# SensWear_MCU.net
KiCad netlist of a schematic drawn in Altium Designer
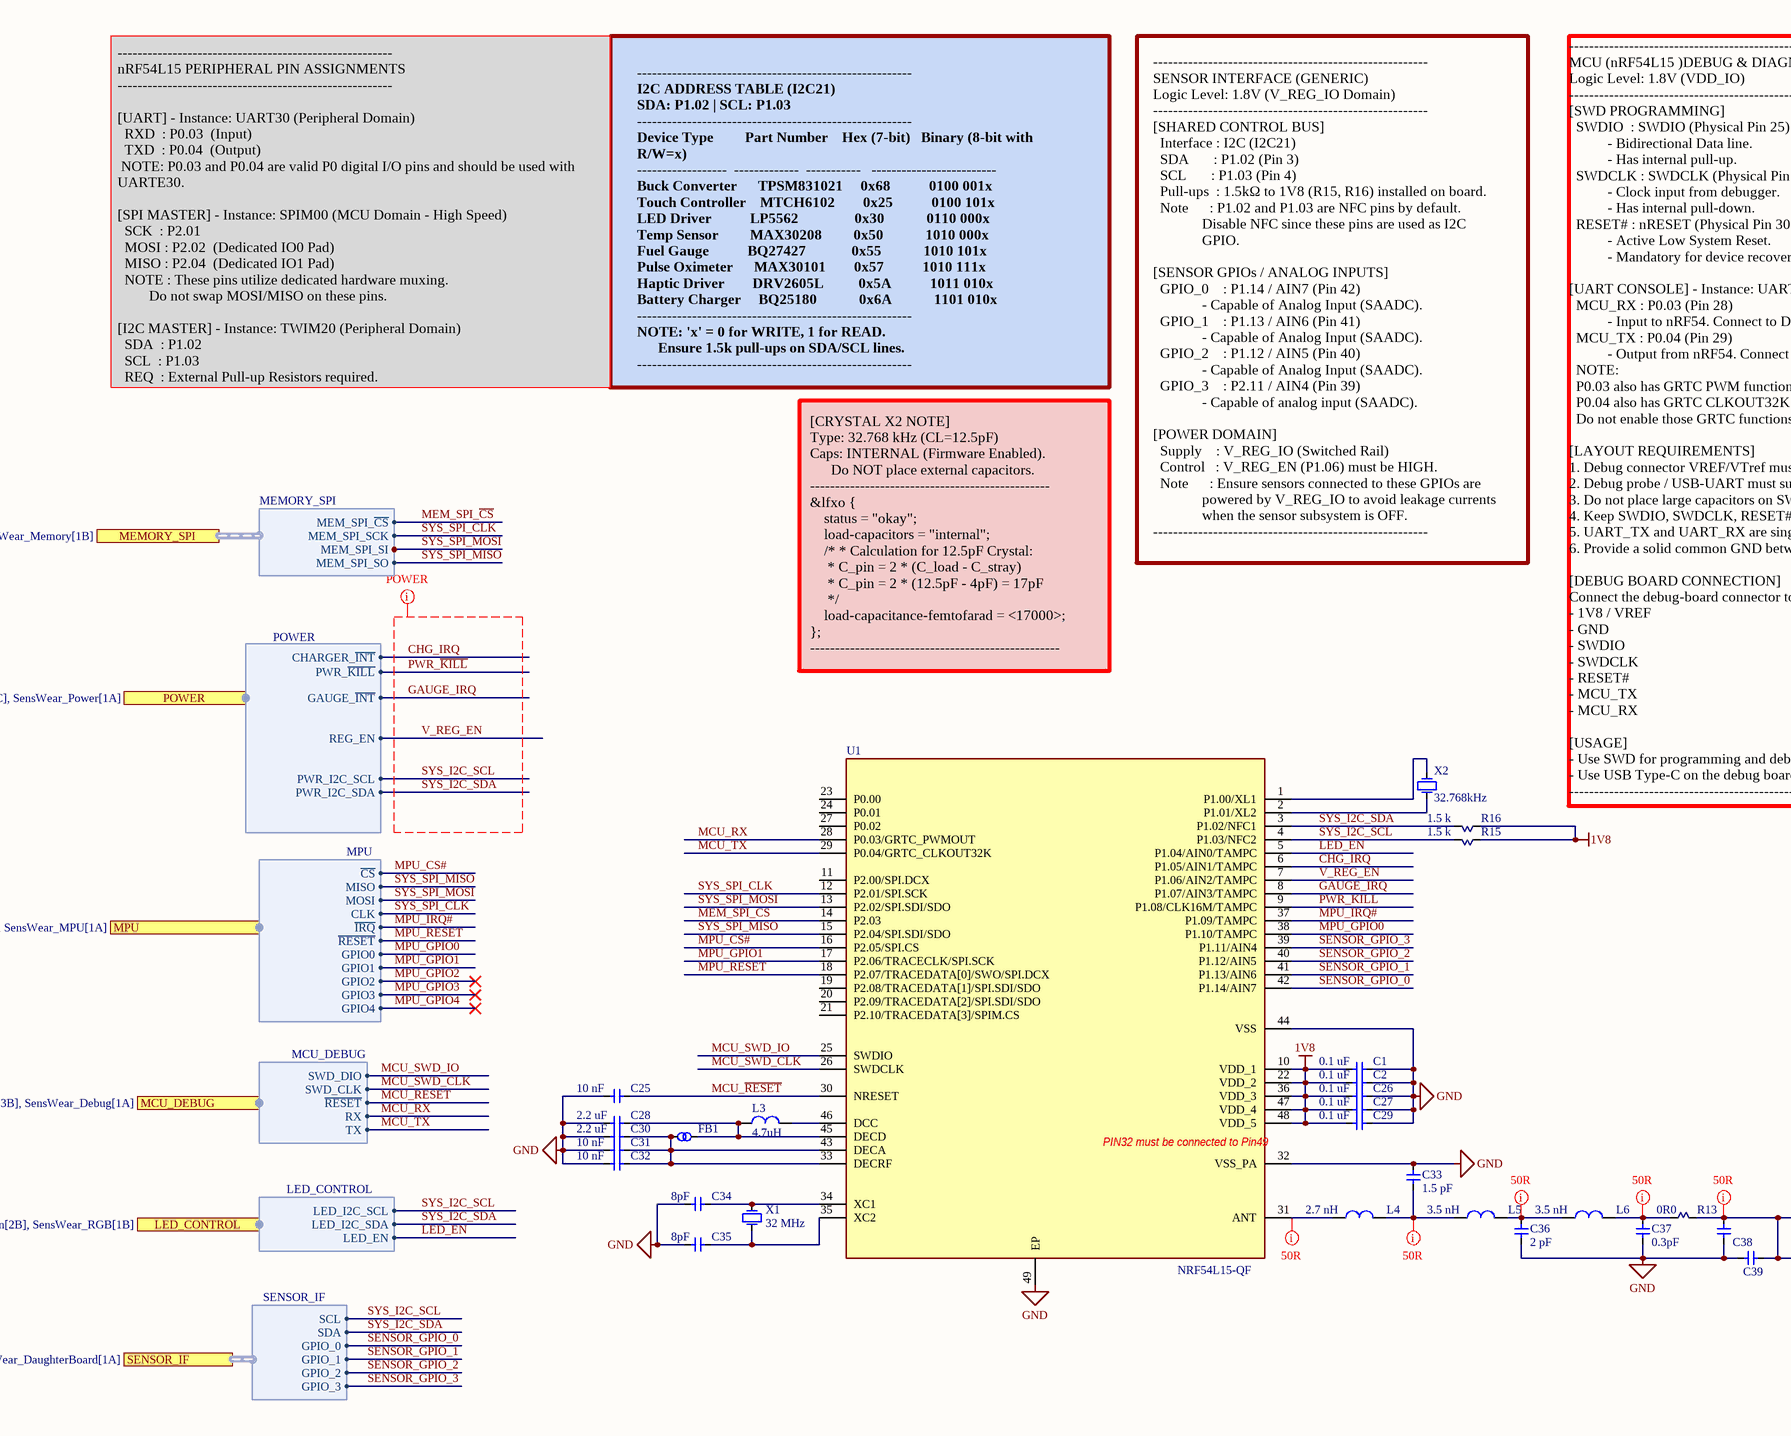
[diagram p0: SensWear_MCU.SchDoc, left]
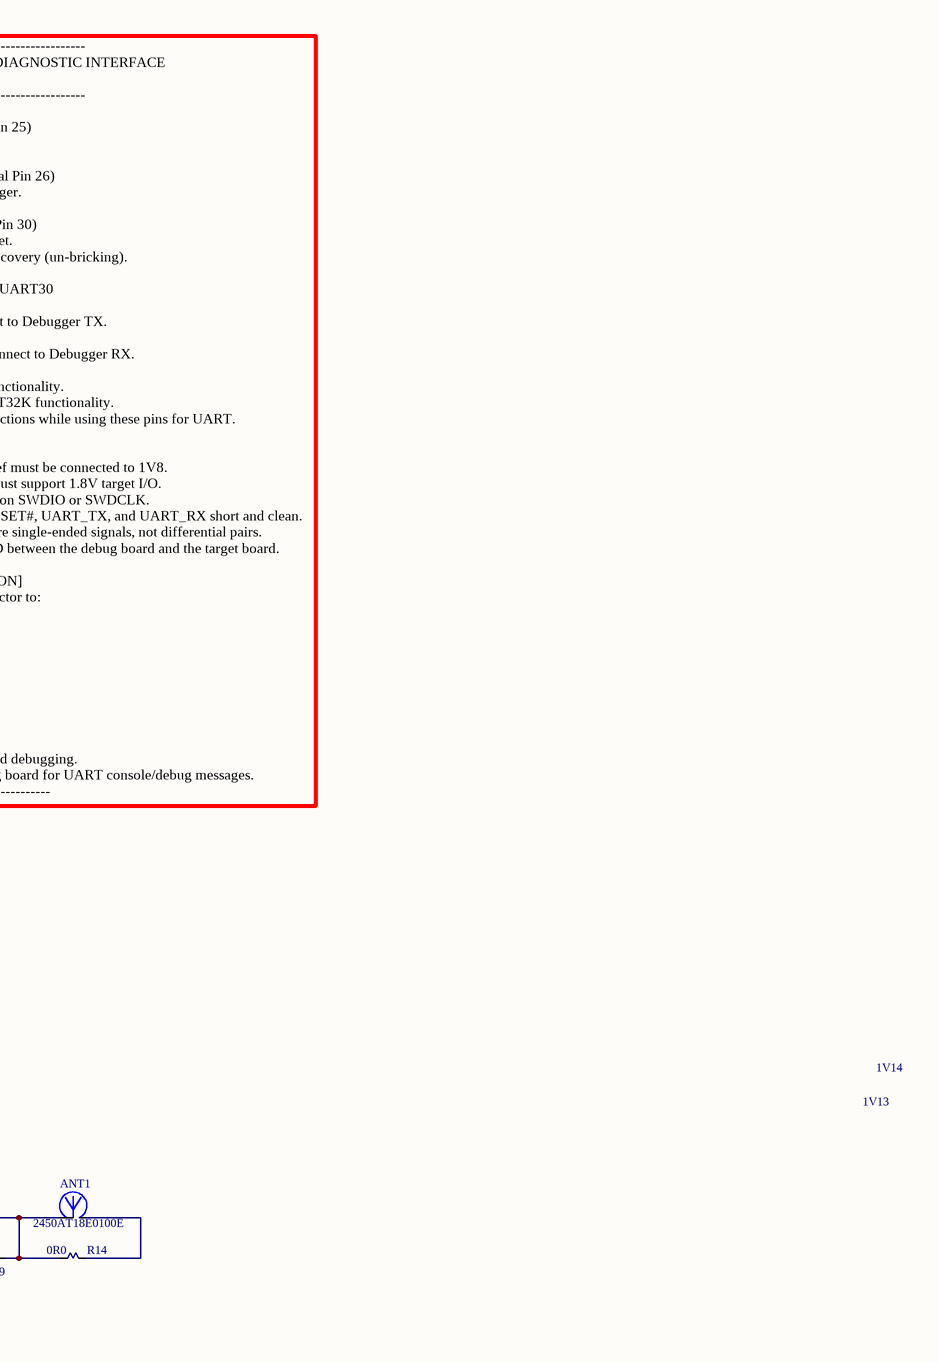
[diagram p1: SensWear_MCU.SchDoc, right]

(export (version "E")
  (design (tool "Eeschema 10.0.6"))
  (components
    (comp (ref "ANT1")
      (value "2450AT18E0100E")
      (footprint "ANTC3216X130N")
      (description "7 Inch Reel / Mini 2.45Ghz Chip Antenna")
      (fields (field (name "MANUFACTURER") "Johanson") (field (name "CHECKED") "TRUE"))
      (libsource (lib "SensWearComponents") (part "2450AT18E0100E"))
    )
    (comp (ref "C1")
      (value "0.1 uF")
      (footprint "CAPC1005X05N")
      (description "CAP CER 0.1UF 16V X5R 0402")
      (fields
        (field (name "MANUFACTURER") "Murata Electronics")
        (field (name "MANUFACTURER PART NUMBER") "GRM155R61C104KA88D")
      )
      (libsource (lib "SensWearComponents") (part "GRM155R61C104KA88D__2"))
    )
    (comp (ref "C2")
      (value "0.1 uF")
      (footprint "CAPC1005X05N")
      (description "CAP CER 0.1UF 16V X5R 0402")
      (fields
        (field (name "MANUFACTURER") "Murata Electronics")
        (field (name "MANUFACTURER PART NUMBER") "GRM155R61C104KA88D")
      )
      (libsource (lib "SensWearComponents") (part "GRM155R61C104KA88D__2"))
    )
    (comp (ref "C25")
      (value "10 nF")
      (footprint "CAPC1005X05N")
      (description "CAP CER 10000PF 50V X7R 0402")
      (fields
        (field (name "MANUFACTURER") "Murata Electronics North America")
        (field (name "MANUFACTURER PART NUMBER") "GRM155R71H103KA88D")
      )
      (libsource (lib "SensWearComponents") (part "GRM155R71H103KA88D"))
    )
    (comp (ref "C26")
      (value "0.1 uF")
      (footprint "CAPC1005X05N")
      (description "CAP CER 0.1UF 16V X5R 0402")
      (fields
        (field (name "MANUFACTURER") "Murata Electronics")
        (field (name "MANUFACTURER PART NUMBER") "GRM155R61C104KA88D")
      )
      (libsource (lib "SensWearComponents") (part "GRM155R61C104KA88D__2"))
    )
    (comp (ref "C27")
      (value "0.1 uF")
      (footprint "CAPC1005X05N")
      (description "CAP CER 0.1UF 16V X5R 0402")
      (fields
        (field (name "MANUFACTURER") "Murata Electronics")
        (field (name "MANUFACTURER PART NUMBER") "GRM155R61C104KA88D")
      )
      (libsource (lib "SensWearComponents") (part "GRM155R61C104KA88D__2"))
    )
    (comp (ref "C28")
      (value "2.2 uF")
      (footprint "CAPC1005X05N")
      (description "CAP CER 2.2UF 10V X5R 0402")
      (fields
        (field (name "MANUFACTURER") "Murata Electronics North America")
        (field (name "MANUFACTURER PART NUMBER") "GRM155R61A225KE95D")
      )
      (libsource (lib "SensWearComponents") (part "GRM155R61A225KE95D"))
    )
    (comp (ref "C29")
      (value "0.1 uF")
      (footprint "CAPC1005X05N")
      (description "CAP CER 0.1UF 16V X5R 0402")
      (fields
        (field (name "MANUFACTURER") "Murata Electronics")
        (field (name "MANUFACTURER PART NUMBER") "GRM155R61C104KA88D")
      )
      (libsource (lib "SensWearComponents") (part "GRM155R61C104KA88D__2"))
    )
    (comp (ref "C30")
      (value "2.2 uF")
      (footprint "CAPC1005X05N")
      (description "CAP CER 2.2UF 10V X5R 0402")
      (fields
        (field (name "MANUFACTURER") "Murata Electronics North America")
        (field (name "MANUFACTURER PART NUMBER") "GRM155R61A225KE95D")
      )
      (libsource (lib "SensWearComponents") (part "GRM155R61A225KE95D"))
    )
    (comp (ref "C31")
      (value "10 nF")
      (footprint "CAPC1005X05N")
      (description "CAP CER 10000PF 50V X7R 0402")
      (fields
        (field (name "MANUFACTURER") "Murata Electronics North America")
        (field (name "MANUFACTURER PART NUMBER") "GRM155R71H103KA88D")
      )
      (libsource (lib "SensWearComponents") (part "GRM155R71H103KA88D"))
    )
    (comp (ref "C32")
      (value "10 nF")
      (footprint "CAPC1005X05N")
      (description "CAP CER 10000PF 50V X7R 0402")
      (fields
        (field (name "MANUFACTURER") "Murata Electronics North America")
        (field (name "MANUFACTURER PART NUMBER") "GRM155R71H103KA88D")
      )
      (libsource (lib "SensWearComponents") (part "GRM155R71H103KA88D"))
    )
    (comp (ref "C33")
      (value "1.5 pF")
      (footprint "CAPC1005X05N")
      (description "Multilayer Ceramic Capacitor, 1.5 pF, 50 V, ï¿½ 0.1pF, C0G (NP0), 0402 [1005 Metric]")
      (fields
        (field (name "MANUFACTURER") "Murata")
        (field (name "MANUFACTURER PART NUMBER") "GJM1555C1H1R5BB01D")
      )
      (libsource (lib "SensWearComponents") (part "GJM1555C1H1R5BB01D"))
    )
    (comp (ref "C34")
      (value "8pF")
      (footprint "CAPC1005X05N")
      (description "Multilayer Ceramic Capacitors MLCC - SMD/SMT 0402 8.0pF 50volts C0G +/-0.05pF")
      (fields
        (field (name "MANUFACTURER") "Murata")
        (field (name "MANUFACTURER PART NUMBER") "GRM1555C1H8R0BA01D")
      )
      (libsource (lib "SensWearComponents") (part "GRM1555C1H8R0BA01D"))
    )
    (comp (ref "C35")
      (value "8pF")
      (footprint "CAPC1005X05N")
      (description "Multilayer Ceramic Capacitors MLCC - SMD/SMT 0402 8.0pF 50volts C0G +/-0.05pF")
      (fields
        (field (name "MANUFACTURER") "Murata")
        (field (name "MANUFACTURER PART NUMBER") "GRM1555C1H8R0BA01D")
      )
      (libsource (lib "SensWearComponents") (part "GRM1555C1H8R0BA01D"))
    )
    (comp (ref "C36")
      (value "2 pF")
      (footprint "CAPC1005X05N")
      (description "0402 2 pF 50V ±0.05 pF Tolerance C0G SMT Multilayer Ceramic Capacitor")
      (fields
        (field (name "MANUFACTURER") "Murata")
        (field (name "MANUFACTURER PART NUMBER") "GJM1555C1H2R0WB01D")
      )
      (libsource (lib "SensWearComponents") (part "GJM1555C1H2R0WB01D"))
    )
    (comp (ref "C37")
      (value "0.3pF")
      (footprint "INDC1005X06N")
      (description "0402 0.3 pF 50V ±0.05 pF Tolerance C0G SMT Multilayer Ceramic Capacitor")
      (fields
        (field (name "MANUFACTURER") "Murata")
        (field (name "MANUFACTURER PART NUMBER") "GJM1555C1HR30WB01D")
      )
      (libsource (lib "SensWearComponents") (part "GJM1555C1HR30WB01D"))
    )
    (comp (ref "C38")
      (value "NC")
      (footprint "CAPC1005X05N")
      (libsource (lib "SensWearComponents") (part "CAPACITOR"))
    )
    (comp (ref "C39")
      (value "NC")
      (footprint "CAPC1005X05N")
      (libsource (lib "SensWearComponents") (part "CAPACITOR"))
    )
    (comp (ref "FB1")
      (value "BLM15AG121SN1D")
      (footprint "INDC1005X06N")
      (description "Ferrite Beads Multi-Layer 120Ohm 25% 100MHz 550mA 190mOhm DCR 0402 Paper T/R")
      (fields (field (name "MANUFACTURER") "Murata") (field (name "TOLERANCE") "25%"))
      (libsource (lib "SensWearComponents") (part "BLM15AG121SN1D"))
    )
    (comp (ref "L3")
      (value "4.7uH")
      (footprint "INDC1005X06N")
      (description "Inductor Power Chip Shielded Multi-Layer 4.7uH 20% 1MHz Ferrite 0.08A 0.78Ohm DCR 0603 T/R")
      (fields
        (field (name "MANUFACTURER") "Murata")
        (field (name "MANUFACTURER PART NUMBER") "LQM18FN4R7M00D")
      )
      (libsource (lib "SensWearComponents") (part "LQM18FN4R7M00D"))
    )
    (comp (ref "L4")
      (value "2.7 nH")
      (footprint "INDC1005X06N")
      (description "Inductor Chip 2.7nH 0.1nH Tolerance 2-Pin 0402 Paper T/R")
      (fields
        (field (name "MANUFACTURER") "Murata")
        (field (name "MANUFACTURER PART NUMBER") "LQG15WH2N7B02D")
      )
      (libsource (lib "SensWearComponents") (part "LQG15WH2N7B02D"))
    )
    (comp (ref "L5")
      (value "3.5 nH")
      (footprint "INDC1005X06N")
      (description "Inductor Chip 3.5nH 0.1nH Tolerance 2-Pin 0402 Paper T/R")
      (fields
        (field (name "MANUFACTURER") "Murata")
        (field (name "MANUFACTURER PART NUMBER") "LQG15WH3N5B02D")
      )
      (libsource (lib "SensWearComponents") (part "LQG15WH3N5B02D"))
    )
    (comp (ref "L6")
      (value "3.5 nH")
      (footprint "INDC1005X06N")
      (description "Inductor Chip 3.5nH 0.1nH Tolerance 2-Pin 0402 Paper T/R")
      (fields
        (field (name "MANUFACTURER") "Murata")
        (field (name "MANUFACTURER PART NUMBER") "LQG15WH3N5B02D")
      )
      (libsource (lib "SensWearComponents") (part "LQG15WH3N5B02D"))
    )
    (comp (ref "R13")
      (value "0R0")
      (footprint "RESC1005X04N")
      (description "RES SMD 0.0OHM JUMPER 1/10W 0402")
      (fields
        (field (name "MANUFACTURER") "Panasonic Electronic Components")
        (field (name "MANUFACTURER PART NUMBER") "ERJ-2GE0R00X")
      )
      (libsource (lib "SensWearComponents") (part "ERJ-2GE0R00X"))
    )
    (comp (ref "R14")
      (value "0R0")
      (footprint "RESC1005X04N")
      (description "RES SMD 0.0OHM JUMPER 1/10W 0402")
      (fields
        (field (name "MANUFACTURER") "Panasonic Electronic Components")
        (field (name "MANUFACTURER PART NUMBER") "ERJ-2GE0R00X")
      )
      (libsource (lib "SensWearComponents") (part "ERJ-2GE0R00X"))
    )
    (comp (ref "R15")
      (value "1.5 k")
      (footprint "RESC1005X04N")
      (description "RES SMD 1.5K OHM 1% 1/10W 0402")
      (fields
        (field (name "MANUFACTURER") "Panasonic Electronic Components")
        (field (name "MANUFACTURER PART NUMBER") "ERJ-2RKF1501X")
      )
      (libsource (lib "SensWearComponents") (part "ERJ-2RKF1501X"))
    )
    (comp (ref "R16")
      (value "1.5 k")
      (footprint "RESC1005X04N")
      (description "RES SMD 1.5K OHM 1% 1/10W 0402")
      (fields
        (field (name "MANUFACTURER") "Panasonic Electronic Components")
        (field (name "MANUFACTURER PART NUMBER") "ERJ-2RKF1501X")
      )
      (libsource (lib "SensWearComponents") (part "ERJ-2RKF1501X"))
    )
    (comp (ref "U1")
      (value "NRF54L15-QF")
      (footprint "QFN40P600X600X95-49N")
      (description "nRF54L15 SoC with Arm Cortex-M33 processor")
      (fields
        (field (name "MANUFACTURER") "Nordic Semiconductor")
        (field (name "MANUFACTURER PART NUMBER") "NRF54L15-QFAA-R")
      )
      (libsource (lib "SensWearComponents") (part "NRF54L15-QFAA-R"))
    )
    (comp (ref "X1")
      (value "32 MHz")
      (footprint "FP-ABM11W-MFG")
      (description "CRYSTAL 32.0000MHZ 8PF SMD, 2x1.6mm, RoHS")
      (fields
        (field (name "MANUFACTURER") "Abracon")
        (field (name "MANUFACTURER PART NUMBER") "ABM11W-32.0000MHZ-8-B1U-T3")
        (field (name "CHECKED") "TRUE")
      )
      (libsource (lib "SensWearComponents") (part "ABM11W-32.0000MHZ-8-B1U-T3"))
    )
    (comp (ref "X2")
      (value "32.768kHz")
      (footprint "Abracon_ABS6_2012X06L")
      (description "CRYSTAL 32.768 KHZ 12.5 PF SMD")
      (fields
        (field (name "MANUFACTURER") "Abracon Corporation")
        (field (name "MANUFACTURER PART NUMBER") "ABS06-32.768KHZ-1-T")
      )
      (libsource (lib "SensWearComponents") (part "ABS06-32.768KHZ-1-T"))
    )
  )
  (nets
    (net (code "7") (name "/CHG_IRQ") (class "Default")
      (node (ref "U1") (pin "6") (pinfunction "P1.05/AIN1/TAMPC_6") (pintype "passive"))
    )
    (net (code "8") (name "/GAUGE_IRQ") (class "Default")
      (node (ref "U1") (pin "8") (pinfunction "P1.07/AIN3/TAMPC_8") (pintype "passive"))
    )
    (net (code "9") (name "/LED_EN") (class "Default")
      (node (ref "U1") (pin "5") (pinfunction "P1.04/AIN0/TAMPC_5") (pintype "passive"))
    )
    (net (code "10") (name "/MCU_RX") (class "Default")
      (node (ref "U1") (pin "28") (pinfunction "P0.03/GRTC_PWMOUT_28") (pintype "passive"))
    )
    (net (code "11") (name "/MCU_SWD_CLK") (class "Default")
      (node (ref "U1") (pin "26") (pinfunction "SWDCLK_26") (pintype "passive"))
    )
    (net (code "12") (name "/MCU_SWD_IO") (class "Default")
      (node (ref "U1") (pin "25") (pinfunction "SWDIO_25") (pintype "passive"))
    )
    (net (code "13") (name "/MCU_TX") (class "Default")
      (node (ref "U1") (pin "29") (pinfunction "P0.04/GRTC_CLKOUT32K_29") (pintype "passive"))
    )
    (net (code "14") (name "/MCU_~{RESET}") (class "Default")
      (node (ref "C25") (pin "2") (pinfunction "2_2") (pintype "passive"))
      (node (ref "U1") (pin "30") (pinfunction "NRESET_30") (pintype "passive"))
    )
    (net (code "15") (name "/MEM_SPI_~{CS}") (class "Default")
      (node (ref "U1") (pin "14") (pinfunction "P2.03_14") (pintype "passive"))
    )
    (net (code "16") (name "/MPU_CS#") (class "Default")
      (node (ref "U1") (pin "16") (pinfunction "P2.05/SPI.CS_16") (pintype "passive"))
    )
    (net (code "17") (name "/MPU_GPIO0") (class "Default")
      (node (ref "U1") (pin "38") (pinfunction "P1.10/TAMPC_38") (pintype "passive"))
    )
    (net (code "18") (name "/MPU_GPIO1") (class "Default")
      (node (ref "U1") (pin "17") (pinfunction "P2.06/TRACECLK/SPI.SCK_17") (pintype "passive"))
    )
    (net (code "22") (name "/MPU_IRQ#") (class "Default")
      (node (ref "U1") (pin "37") (pinfunction "P1.09/TAMPC_37") (pintype "passive"))
    )
    (net (code "23") (name "/MPU_~{RESET}") (class "Default")
      (node (ref "U1") (pin "18") (pinfunction "P2.07/TRACEDATA[0]/SWO/SPI.DCX_18") (pintype "passive"))
    )
    (net (code "24") (name "/PWR_~{KILL}") (class "Default")
      (node (ref "U1") (pin "9") (pinfunction "P1.08/CLK16M/TAMPC_9") (pintype "passive"))
    )
    (net (code "25") (name "/SENSOR_GPIO_0") (class "Default")
      (node (ref "U1") (pin "42") (pinfunction "P1.14/AIN7_42") (pintype "passive"))
    )
    (net (code "26") (name "/SENSOR_GPIO_1") (class "Default")
      (node (ref "U1") (pin "41") (pinfunction "P1.13/AIN6_41") (pintype "passive"))
    )
    (net (code "27") (name "/SENSOR_GPIO_2") (class "Default")
      (node (ref "U1") (pin "40") (pinfunction "P1.12/AIN5_40") (pintype "passive"))
    )
    (net (code "28") (name "/SENSOR_GPIO_3") (class "Default")
      (node (ref "U1") (pin "39") (pinfunction "P1.11/AIN4_39") (pintype "passive"))
    )
    (net (code "29") (name "/SYS_I2C_SCL") (class "Default")
      (node (ref "R15") (pin "2") (pinfunction "2_2") (pintype "passive"))
      (node (ref "U1") (pin "4") (pinfunction "P1.03/NFC2_4") (pintype "passive"))
    )
    (net (code "30") (name "/SYS_I2C_SDA") (class "Default")
      (node (ref "R16") (pin "2") (pinfunction "2_2") (pintype "passive"))
      (node (ref "U1") (pin "3") (pinfunction "P1.02/NFC1_3") (pintype "passive"))
    )
    (net (code "31") (name "/SYS_SPI_CLK") (class "Default")
      (node (ref "U1") (pin "12") (pinfunction "P2.01/SPI.SCK_12") (pintype "passive"))
    )
    (net (code "32") (name "/SYS_SPI_MISO") (class "Default")
      (node (ref "U1") (pin "15") (pinfunction "P2.04/SPI.SDI/SDO_15") (pintype "passive"))
    )
    (net (code "33") (name "/SYS_SPI_MOSI") (class "Default")
      (node (ref "U1") (pin "13") (pinfunction "P2.02/SPI.SDI/SDO_13") (pintype "passive"))
    )
    (net (code "34") (name "/V_REG_EN") (class "Default")
      (node (ref "U1") (pin "7") (pinfunction "P1.06/AIN2/TAMPC_7") (pintype "passive"))
    )
    (net (code "41") (name "1V8") (class "Default")
      (node (ref "C1") (pin "1") (pinfunction "1_1") (pintype "passive"))
      (node (ref "C2") (pin "1") (pinfunction "1_1") (pintype "passive"))
      (node (ref "C26") (pin "1") (pinfunction "1_1") (pintype "passive"))
      (node (ref "C27") (pin "1") (pinfunction "1_1") (pintype "passive"))
      (node (ref "C29") (pin "1") (pinfunction "1_1") (pintype "passive"))
      (node (ref "R15") (pin "1") (pinfunction "1_1") (pintype "passive"))
      (node (ref "R16") (pin "1") (pinfunction "1_1") (pintype "passive"))
      (node (ref "U1") (pin "10") (pinfunction "VDD_1_10") (pintype "passive"))
      (node (ref "U1") (pin "22") (pinfunction "VDD_2_22") (pintype "passive"))
      (node (ref "U1") (pin "36") (pinfunction "VDD_3_36") (pintype "passive"))
      (node (ref "U1") (pin "47") (pinfunction "VDD_4_47") (pintype "passive"))
      (node (ref "U1") (pin "48") (pinfunction "VDD_5_48") (pintype "passive"))
    )
    (net (code "42") (name "GND") (class "Default")
      (node (ref "C1") (pin "2") (pinfunction "2_2") (pintype "passive"))
      (node (ref "C2") (pin "2") (pinfunction "2_2") (pintype "passive"))
      (node (ref "C25") (pin "1") (pinfunction "1_1") (pintype "passive"))
      (node (ref "C26") (pin "2") (pinfunction "2_2") (pintype "passive"))
      (node (ref "C27") (pin "2") (pinfunction "2_2") (pintype "passive"))
      (node (ref "C28") (pin "1") (pinfunction "1_1") (pintype "passive"))
      (node (ref "C29") (pin "2") (pinfunction "2_2") (pintype "passive"))
      (node (ref "C30") (pin "1") (pinfunction "1_1") (pintype "passive"))
      (node (ref "C31") (pin "1") (pinfunction "1_1") (pintype "passive"))
      (node (ref "C32") (pin "1") (pinfunction "1_1") (pintype "passive"))
      (node (ref "C33") (pin "2") (pinfunction "2_2") (pintype "passive"))
      (node (ref "C34") (pin "1") (pinfunction "1_1") (pintype "passive"))
      (node (ref "C35") (pin "1") (pinfunction "1_1") (pintype "passive"))
      (node (ref "C36") (pin "1") (pinfunction "1_1") (pintype "passive"))
      (node (ref "C37") (pin "1") (pinfunction "1_1") (pintype "passive"))
      (node (ref "C38") (pin "1") (pinfunction "1_1") (pintype "passive"))
      (node (ref "C39") (pin "2") (pinfunction "2_2") (pintype "passive"))
      (node (ref "U1") (pin "32") (pinfunction "VSS_PA_32") (pintype "passive"))
      (node (ref "U1") (pin "44") (pinfunction "VSS_44") (pintype "passive"))
      (node (ref "U1") (pin "49") (pinfunction "EP_49") (pintype "passive"))
    )
    (net (code "43") (name "Net-(ANT1-Pad1)") (class "Default")
      (node (ref "ANT1") (pin "1") (pinfunction "1_1") (pintype "passive"))
      (node (ref "C38") (pin "2") (pinfunction "2_2") (pintype "passive"))
      (node (ref "C39") (pin "1") (pinfunction "1_1") (pintype "passive"))
      (node (ref "R13") (pin "2") (pinfunction "2_2") (pintype "passive"))
      (node (ref "R14") (pin "1") (pinfunction "1_1") (pintype "passive"))
    )
    (net (code "44") (name "Net-(ANT1-Pad2)") (class "Default")
      (node (ref "ANT1") (pin "2") (pinfunction "2_2") (pintype "passive"))
      (node (ref "R14") (pin "2") (pinfunction "2_2") (pintype "passive"))
    )
    (net (code "45") (name "Net-(C33-Pad1)") (class "Default")
      (node (ref "C33") (pin "1") (pinfunction "1_1") (pintype "passive"))
      (node (ref "L4") (pin "2") (pinfunction "2_2") (pintype "passive"))
      (node (ref "L5") (pin "1") (pinfunction "1_1") (pintype "passive"))
    )
    (net (code "46") (name "Net-(C36-Pad2)") (class "Default")
      (node (ref "C36") (pin "2") (pinfunction "2_2") (pintype "passive"))
      (node (ref "L5") (pin "2") (pinfunction "2_2") (pintype "passive"))
      (node (ref "L6") (pin "1") (pinfunction "1_1") (pintype "passive"))
    )
    (net (code "47") (name "Net-(C37-Pad2)") (class "Default")
      (node (ref "C37") (pin "2") (pinfunction "2_2") (pintype "passive"))
      (node (ref "L6") (pin "2") (pinfunction "2_2") (pintype "passive"))
      (node (ref "R13") (pin "1") (pinfunction "1_1") (pintype "passive"))
    )
    (net (code "48") (name "Net-(U1-ANT)") (class "Default")
      (node (ref "L4") (pin "1") (pinfunction "1_1") (pintype "passive"))
      (node (ref "U1") (pin "31") (pinfunction "ANT_31") (pintype "passive"))
    )
    (net (code "49") (name "Net-(U1-DCC)") (class "Default")
      (node (ref "L3") (pin "2") (pinfunction "2_2") (pintype "passive"))
      (node (ref "U1") (pin "46") (pinfunction "DCC_46") (pintype "passive"))
    )
    (net (code "50") (name "Net-(U1-DECA)") (class "Default")
      (node (ref "C30") (pin "2") (pinfunction "2_2") (pintype "passive"))
      (node (ref "C31") (pin "2") (pinfunction "2_2") (pintype "passive"))
      (node (ref "C32") (pin "2") (pinfunction "2_2") (pintype "passive"))
      (node (ref "FB1") (pin "1") (pinfunction "1_1") (pintype "passive"))
      (node (ref "U1") (pin "33") (pinfunction "DECRF_33") (pintype "passive"))
      (node (ref "U1") (pin "43") (pinfunction "DECA_43") (pintype "passive"))
    )
    (net (code "51") (name "Net-(U1-DECD)") (class "Default")
      (node (ref "C28") (pin "2") (pinfunction "2_2") (pintype "passive"))
      (node (ref "FB1") (pin "2") (pinfunction "2_2") (pintype "passive"))
      (node (ref "L3") (pin "1") (pinfunction "1_1") (pintype "passive"))
      (node (ref "U1") (pin "45") (pinfunction "DECD_45") (pintype "passive"))
    )
    (net (code "52") (name "Net-(U1-P1.00{slash}XL1)") (class "Default")
      (node (ref "U1") (pin "1") (pinfunction "P1.00/XL1_1") (pintype "passive"))
      (node (ref "X2") (pin "2") (pinfunction "OSC2_2") (pintype "passive"))
    )
    (net (code "53") (name "Net-(U1-P1.01{slash}XL2)") (class "Default")
      (node (ref "U1") (pin "2") (pinfunction "P1.01/XL2_2") (pintype "passive"))
      (node (ref "X2") (pin "1") (pinfunction "OSC1_1") (pintype "passive"))
    )
    (net (code "54") (name "Net-(U1-XC1)") (class "Default")
      (node (ref "C34") (pin "2") (pinfunction "2_2") (pintype "passive"))
      (node (ref "U1") (pin "34") (pinfunction "XC1_34") (pintype "passive"))
      (node (ref "X1") (pin "3") (pinfunction "OSC2_3") (pintype "passive"))
    )
    (net (code "55") (name "Net-(U1-XC2)") (class "Default")
      (node (ref "C35") (pin "2") (pinfunction "2_2") (pintype "passive"))
      (node (ref "U1") (pin "35") (pinfunction "XC2_35") (pintype "passive"))
      (node (ref "X1") (pin "1") (pinfunction "OSC1_1") (pintype "passive"))
    )
    (net (code "56") (name "unconnected-(U1-P0.00-Pad23)") (class "Default")
      (node (ref "U1") (pin "23") (pinfunction "P0.00_23") (pintype "passive"))
    )
    (net (code "57") (name "unconnected-(U1-P0.01-Pad24)") (class "Default")
      (node (ref "U1") (pin "24") (pinfunction "P0.01_24") (pintype "passive"))
    )
    (net (code "58") (name "unconnected-(U1-P0.02-Pad27)") (class "Default")
      (node (ref "U1") (pin "27") (pinfunction "P0.02_27") (pintype "passive"))
    )
    (net (code "59") (name "unconnected-(U1-P2.00{slash}SPI.DCX-Pad11)") (class "Default")
      (node (ref "U1") (pin "11") (pinfunction "P2.00/SPI.DCX_11") (pintype "passive"))
    )
    (net (code "60") (name "unconnected-(U1-P2.08{slash}TRACEDATA[1]{slash}SPI.SDI{slash}SDO-Pad19)") (class "Default")
      (node (ref "U1") (pin "19") (pinfunction "P2.08/TRACEDATA[1]/SPI.SDI/SDO_19") (pintype "passive"))
    )
    (net (code "61") (name "unconnected-(U1-P2.09{slash}TRACEDATA[2]{slash}SPI.SDI{slash}SDO-Pad20)") (class "Default")
      (node (ref "U1") (pin "20") (pinfunction "P2.09/TRACEDATA[2]/SPI.SDI/SDO_20") (pintype "passive"))
    )
    (net (code "62") (name "unconnected-(U1-P2.10{slash}TRACEDATA[3]{slash}SPIM.CS-Pad21)") (class "Default")
      (node (ref "U1") (pin "21") (pinfunction "P2.10/TRACEDATA[3]/SPIM.CS_21") (pintype "passive"))
    )
  )
)
